# schematic.net
KiCad netlist of a schematic drawn in EasyEDA
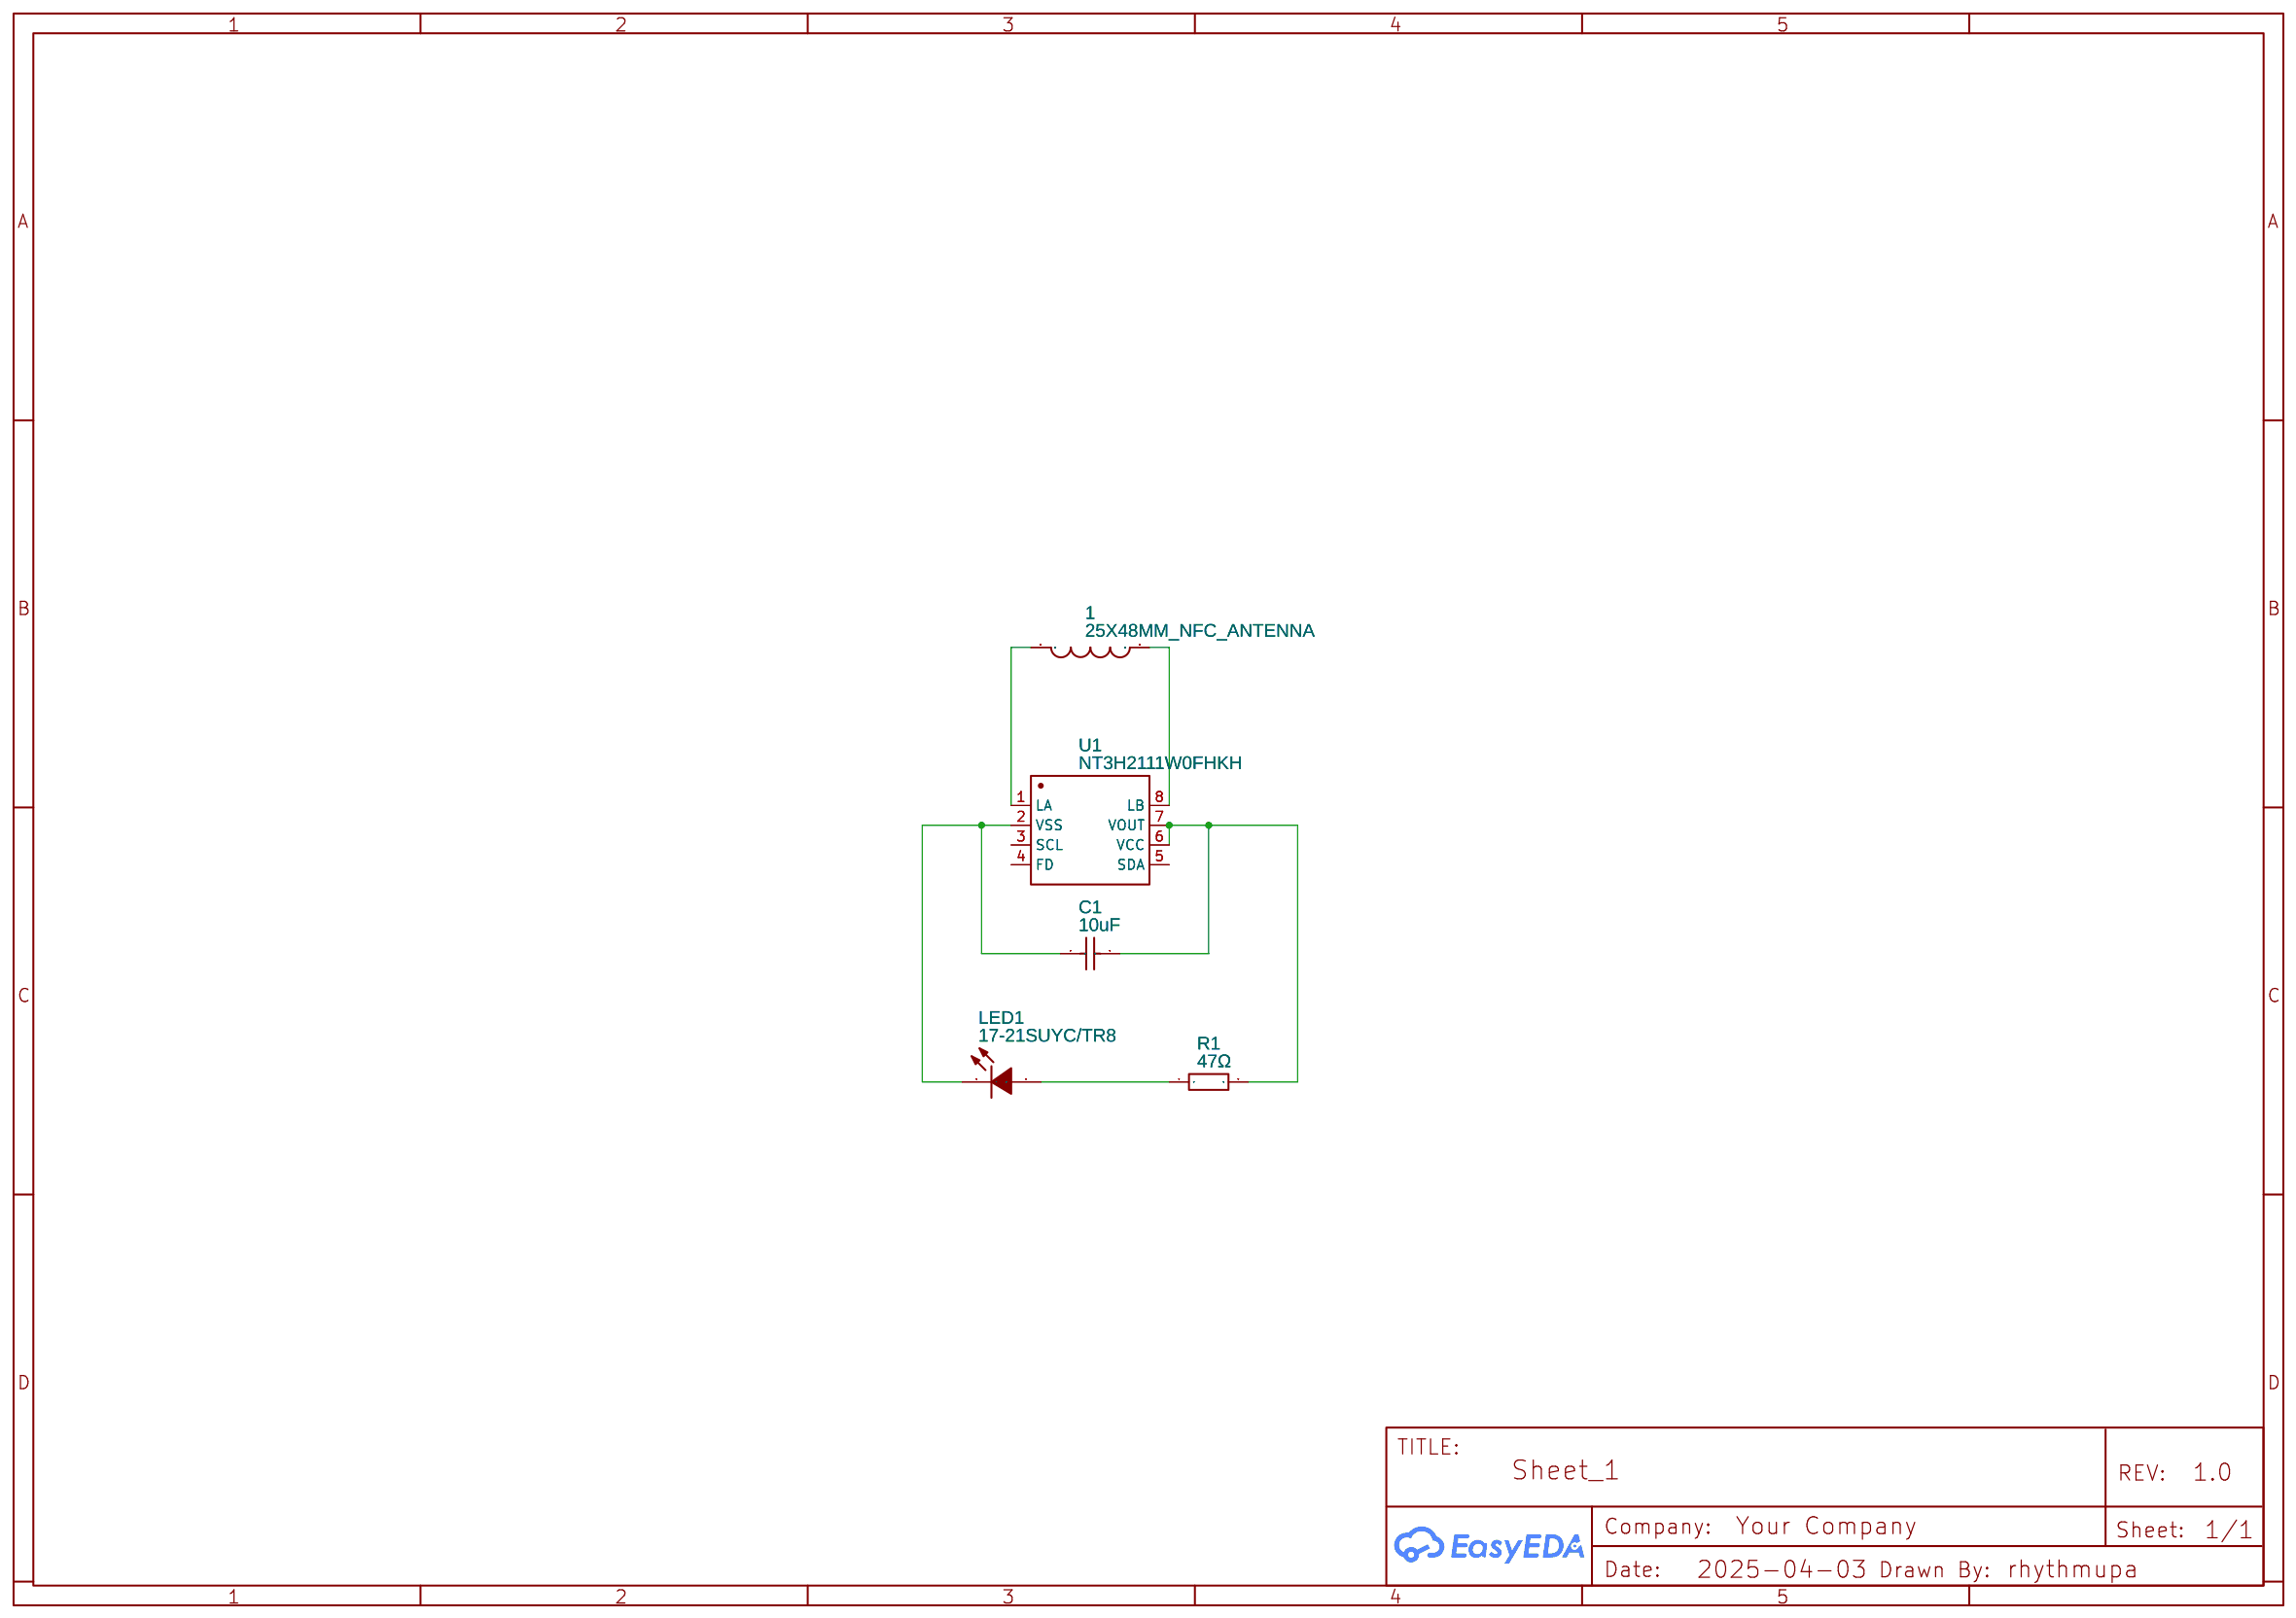
[diagram p0: schematic sheet]

(export (version "E")
  (design (tool "Eeschema 10.0.6"))
  (components
    (comp (ref "1") (value "25X48MM_NFC_ANTENNA") (libsource (lib "") (part "25X48MM_NFC_ANTENNA")))
    (comp (ref "C1")
      (value "10uF")
      (fields
        (field (name "Manufacturer Part") "CL31A106KBHNNNE")
        (field (name "Manufacturer") "SAMSUNG(三星)")
      )
      (libsource (lib "") (part "CL31A106KBHNNNE"))
    )
    (comp (ref "LED1")
      (value "17-21SUYC/TR8")
      (fields (field (name "Manufacturer Part") "KT-0805黄灯") (field (name "Manufacturer") "KENTO"))
      (libsource (lib "") (part "17-21SUYC/TR8"))
    )
    (comp (ref "R1")
      (value "47Ω")
      (fields (field (name "Manufacturer Part") "RC1206FR-0747RL") (field (name "Manufacturer") "YAGEO(国巨)"))
      (libsource (lib "") (part "RC1206FR-0747RL"))
    )
    (comp (ref "U1")
      (value "NT3H2111W0FHKH")
      (fields (field (name "Manufacturer") "NXP(恩智浦)"))
      (libsource (lib "") (part "NT3H2111W0FHKH"))
    )
  )
  (nets
    (net (code "1") (name "Net-(LED1-+)") (class "Default")
      (node (ref "LED1") (pin "1") (pinfunction "+_1") (pintype "unspecified"))
      (node (ref "R1") (pin "1") (pinfunction "1_1") (pintype "input"))
    )
    (net (code "2") (name "Net-(LED1--)") (class "Default")
      (node (ref "C1") (pin "1") (pinfunction "1_1") (pintype "input"))
      (node (ref "LED1") (pin "2") (pinfunction "-_2") (pintype "unspecified"))
      (node (ref "U1") (pin "2") (pinfunction "VSS_2") (pintype "unspecified"))
    )
    (net (code "3") (name "Net-(U1-LA)") (class "Default")
      (node (ref "1") (pin "P$2") (pinfunction "P$2_P$2") (pintype "bidirectional"))
      (node (ref "U1") (pin "1") (pinfunction "LA_1") (pintype "unspecified"))
    )
    (net (code "4") (name "Net-(U1-LB)") (class "Default")
      (node (ref "1") (pin "P$1") (pinfunction "P$1_P$1") (pintype "bidirectional"))
      (node (ref "U1") (pin "8") (pinfunction "LB_8") (pintype "unspecified"))
    )
    (net (code "5") (name "Net-(U1-VCC)") (class "Default")
      (node (ref "C1") (pin "2") (pinfunction "2_2") (pintype "input"))
      (node (ref "R1") (pin "2") (pinfunction "2_2") (pintype "input"))
      (node (ref "U1") (pin "6") (pinfunction "VCC_6") (pintype "unspecified"))
      (node (ref "U1") (pin "7") (pinfunction "VOUT_7") (pintype "unspecified"))
    )
    (net (code "6") (name "unconnected-(U1-FD-Pad4)") (class "Default")
      (node (ref "U1") (pin "4") (pinfunction "FD_4") (pintype "unspecified"))
    )
    (net (code "7") (name "unconnected-(U1-SCL-Pad3)") (class "Default")
      (node (ref "U1") (pin "3") (pinfunction "SCL_3") (pintype "unspecified"))
    )
    (net (code "8") (name "unconnected-(U1-SDA-Pad5)") (class "Default")
      (node (ref "U1") (pin "5") (pinfunction "SDA_5") (pintype "unspecified"))
    )
  )
)
